# AJH_as3320_21_4hp.net
KiCad netlist of a schematic drawn in EAGLE
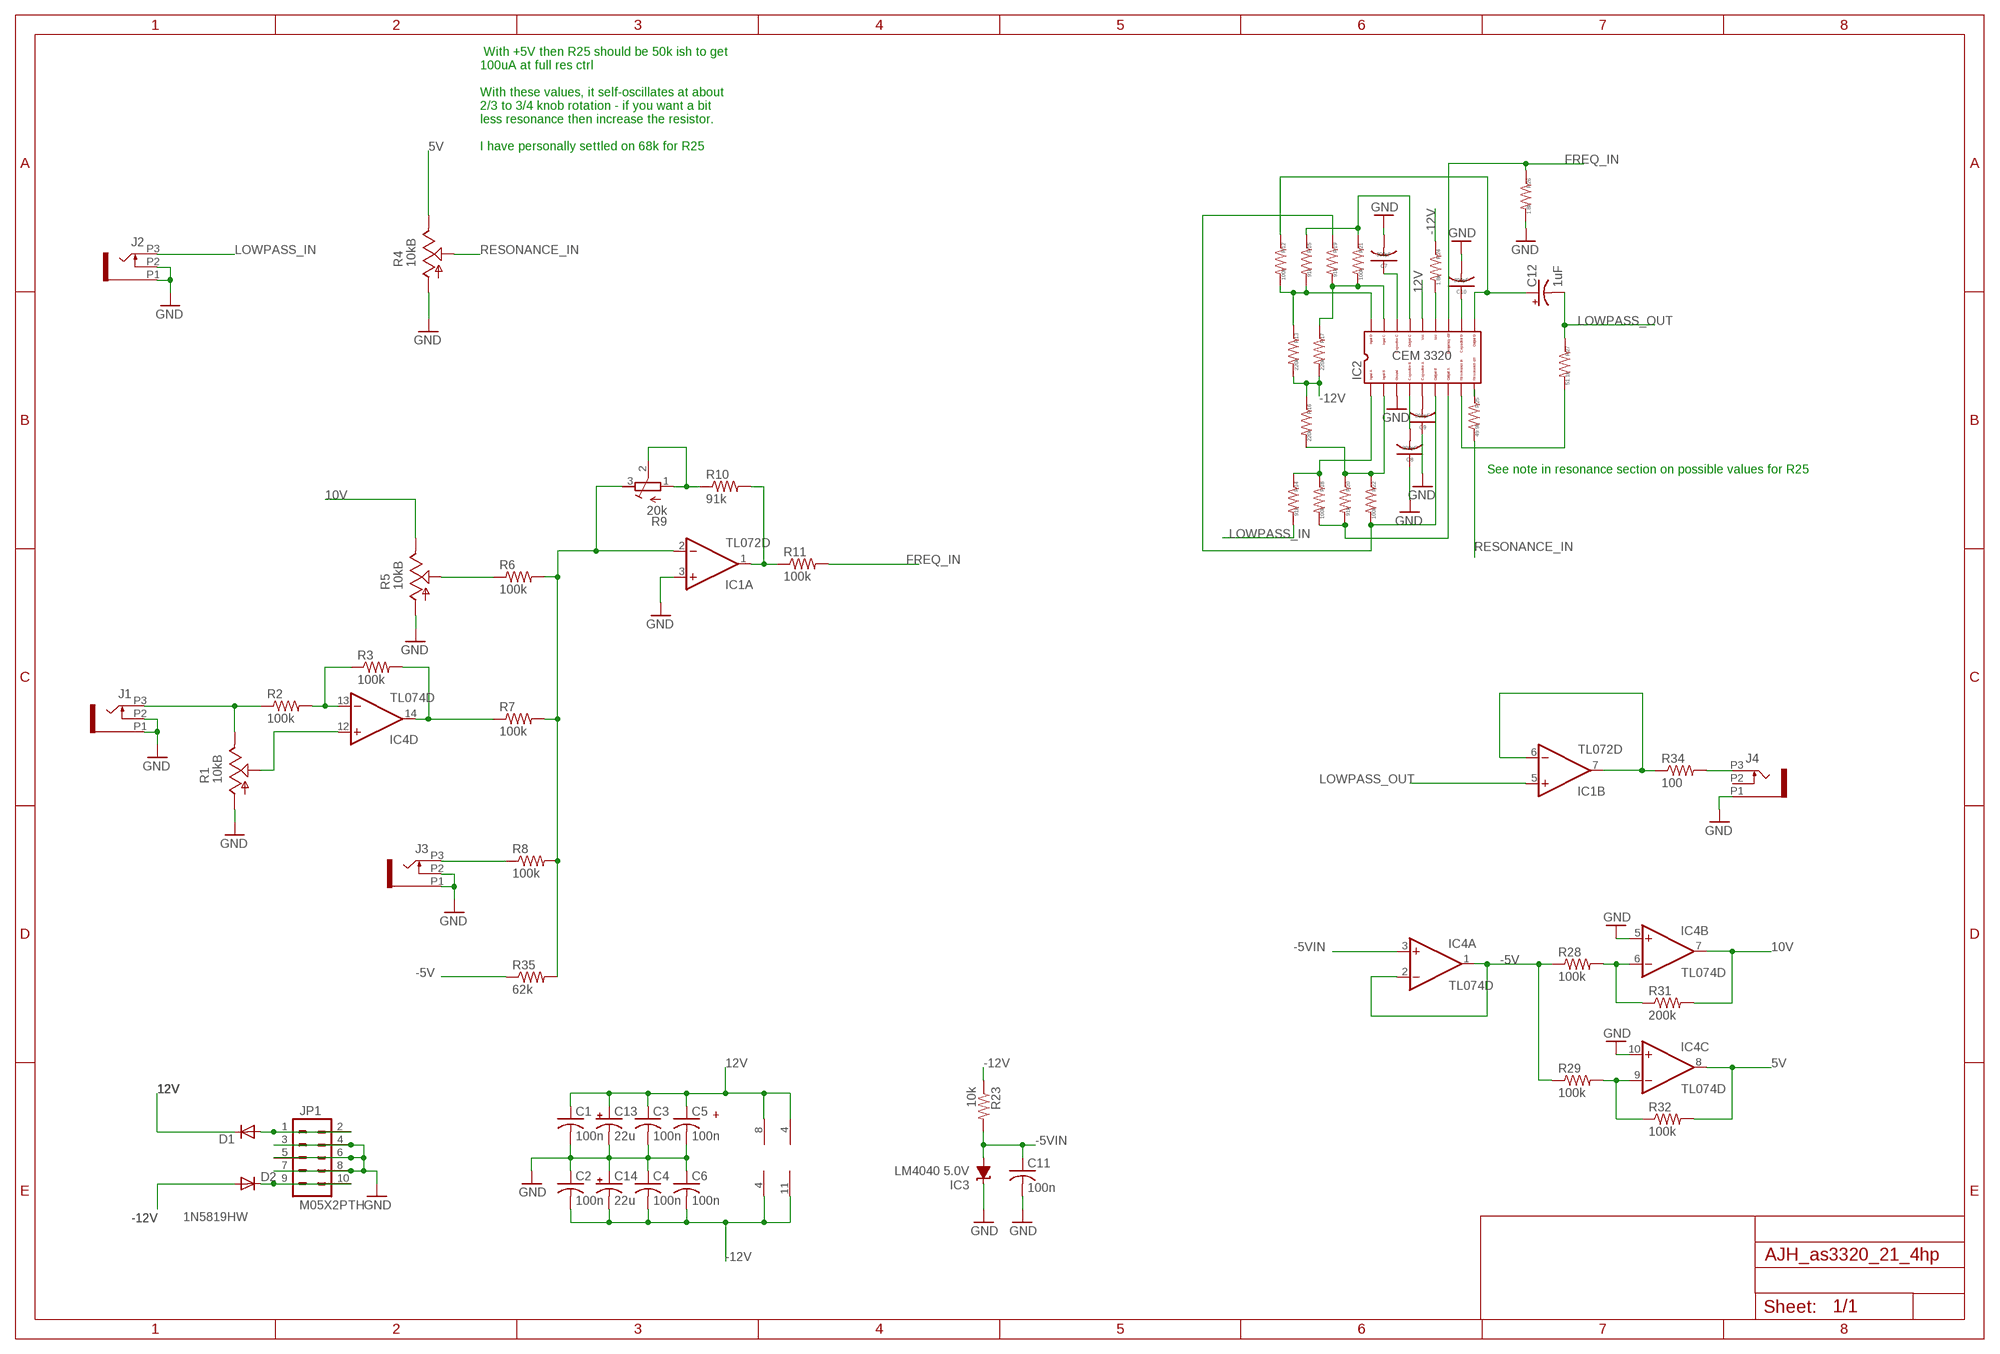
[diagram p0: schematic, sheet 1]

(export (version "E")
  (design (tool "Eeschema 10.0.6"))
  (components
    (comp (ref "C1")
      (value "100n")
      (footprint "eagle-import:C0603")
      (libsource (lib "eagle-import") (part "C-USC0603"))
    )
    (comp (ref "C2")
      (value "100n")
      (footprint "eagle-import:C0603")
      (libsource (lib "eagle-import") (part "C-USC0603"))
    )
    (comp (ref "C3")
      (value "100n")
      (footprint "eagle-import:C0603")
      (libsource (lib "eagle-import") (part "C-USC0603"))
    )
    (comp (ref "C4")
      (value "100n")
      (footprint "eagle-import:C0603")
      (libsource (lib "eagle-import") (part "C-USC0603"))
    )
    (comp (ref "C5")
      (value "100n")
      (footprint "eagle-import:C0603")
      (libsource (lib "eagle-import") (part "C-USC0603"))
    )
    (comp (ref "C6")
      (value "100n")
      (footprint "eagle-import:C0603")
      (libsource (lib "eagle-import") (part "C-USC0603"))
    )
    (comp (ref "C7")
      (value "300pF")
      (footprint "eagle-import:C0603")
      (libsource (lib "eagle-import") (part "rcl_334_C-USC0603"))
    )
    (comp (ref "C8")
      (value "300pF")
      (footprint "eagle-import:C0603")
      (libsource (lib "eagle-import") (part "rcl_334_C-USC0603"))
    )
    (comp (ref "C9")
      (value "300pF")
      (footprint "eagle-import:C0603")
      (libsource (lib "eagle-import") (part "rcl_334_C-USC0603"))
    )
    (comp (ref "C10")
      (value "300pF")
      (footprint "eagle-import:C0603")
      (libsource (lib "eagle-import") (part "rcl_334_C-USC0603"))
    )
    (comp (ref "C11")
      (value "100n")
      (footprint "eagle-import:C0603")
      (libsource (lib "eagle-import") (part "C-USC0603"))
    )
    (comp (ref "C12")
      (value "1uF")
      (footprint "eagle-import:PANASONIC_B")
      (libsource (lib "eagle-import") (part "rcl_334_CPOL-USB"))
    )
    (comp (ref "C13")
      (value "22u")
      (footprint "eagle-import:PANASONIC_B")
      (libsource (lib "eagle-import") (part "CPOL-USB"))
    )
    (comp (ref "C14")
      (value "22u")
      (footprint "eagle-import:PANASONIC_B")
      (libsource (lib "eagle-import") (part "CPOL-USB"))
    )
    (comp (ref "D1")
      (value "1N5819HW")
      (footprint "eagle-import:SOD123")
      (libsource (lib "eagle-import") (part "DIODE-SOD123"))
    )
    (comp (ref "D2")
      (value "1N5819HW")
      (footprint "eagle-import:SOD123")
      (libsource (lib "eagle-import") (part "DIODE-SOD123"))
    )
    (comp (ref "IC1")
      (value "TL072D")
      (footprint "eagle-import:SO08")
      (libsource (lib "eagle-import") (part "TL072D"))
    )
    (comp (ref "IC2")
      (value "CEM3320QFN24")
      (footprint "eagle-import:QFN24")
      (libsource (lib "eagle-import") (part "CEM3320QFN24"))
    )
    (comp (ref "IC3")
      (value "LM4040 5.0V")
      (footprint "eagle-import:DBZ_R-PDSO-G3")
      (libsource (lib "eagle-import") (part "LM4041DBZC12"))
    )
    (comp (ref "IC4")
      (value "TL074D")
      (footprint "eagle-import:SO14")
      (libsource (lib "eagle-import") (part "TL074D"))
    )
    (comp (ref "J1")
      (value "PJ301_THONKICONN6")
      (footprint "eagle-import:WQP_PJ_301M6")
      (libsource (lib "eagle-import") (part "PJ301_THONKICONN6"))
    )
    (comp (ref "J2")
      (value "PJ301_THONKICONN6")
      (footprint "eagle-import:WQP_PJ_301M6")
      (libsource (lib "eagle-import") (part "PJ301_THONKICONN6"))
    )
    (comp (ref "J3")
      (value "PJ301_THONKICONN6")
      (footprint "eagle-import:WQP_PJ_301M6")
      (libsource (lib "eagle-import") (part "PJ301_THONKICONN6"))
    )
    (comp (ref "J4")
      (value "PJ301_THONKICONN6")
      (footprint "eagle-import:WQP_PJ_301M6")
      (libsource (lib "eagle-import") (part "PJ301_THONKICONN6"))
    )
    (comp (ref "JP1")
      (value "M05X2PTH")
      (footprint "eagle-import:AVR_ICSP")
      (libsource (lib "eagle-import") (part "M05X2PTH"))
    )
    (comp (ref "R1")
      (value "10kB")
      (footprint "eagle-import:ALPS_POT_VERTICAL")
      (libsource (lib "eagle-import") (part "POT_USVERTICAL"))
    )
    (comp (ref "R2")
      (value "100k")
      (footprint "eagle-import:R0603")
      (libsource (lib "eagle-import") (part "resistor_R-US_R0603"))
    )
    (comp (ref "R3")
      (value "100k")
      (footprint "eagle-import:R0603")
      (libsource (lib "eagle-import") (part "resistor_R-US_R0603"))
    )
    (comp (ref "R4")
      (value "10kB")
      (footprint "eagle-import:ALPS_POT_VERTICAL")
      (libsource (lib "eagle-import") (part "POT_USVERTICAL"))
    )
    (comp (ref "R5")
      (value "10kB")
      (footprint "eagle-import:ALPS_POT_VERTICAL")
      (libsource (lib "eagle-import") (part "POT_USVERTICAL"))
    )
    (comp (ref "R6")
      (value "100k")
      (footprint "eagle-import:R0603")
      (libsource (lib "eagle-import") (part "resistor_R-US_R0603"))
    )
    (comp (ref "R7")
      (value "100k")
      (footprint "eagle-import:R0603")
      (libsource (lib "eagle-import") (part "resistor_R-US_R0603"))
    )
    (comp (ref "R8")
      (value "100k")
      (footprint "eagle-import:R0603")
      (libsource (lib "eagle-import") (part "resistor_R-US_R0603"))
    )
    (comp (ref "R9")
      (value "20k")
      (footprint "eagle-import:RTRIM3296X")
      (libsource (lib "eagle-import") (part "R-TRIMM3296X"))
    )
    (comp (ref "R10")
      (value "91k")
      (footprint "eagle-import:R0603")
      (libsource (lib "eagle-import") (part "resistor_R-US_R0603"))
    )
    (comp (ref "R11")
      (value "100k")
      (footprint "eagle-import:R0603")
      (libsource (lib "eagle-import") (part "resistor_R-US_R0603"))
    )
    (comp (ref "R12")
      (value "100k")
      (footprint "eagle-import:R0603")
      (libsource (lib "eagle-import") (part "R-US_R0603"))
    )
    (comp (ref "R13")
      (value "220k")
      (footprint "eagle-import:R0603")
      (libsource (lib "eagle-import") (part "R-US_R0603"))
    )
    (comp (ref "R14")
      (value "91k")
      (footprint "eagle-import:R0603")
      (libsource (lib "eagle-import") (part "R-US_R0603"))
    )
    (comp (ref "R15")
      (value "91k")
      (footprint "eagle-import:R0603")
      (libsource (lib "eagle-import") (part "R-US_R0603"))
    )
    (comp (ref "R16")
      (value "220k")
      (footprint "eagle-import:R0603")
      (libsource (lib "eagle-import") (part "R-US_R0603"))
    )
    (comp (ref "R17")
      (value "220k")
      (footprint "eagle-import:R0603")
      (libsource (lib "eagle-import") (part "R-US_R0603"))
    )
    (comp (ref "R18")
      (value "100k")
      (footprint "eagle-import:R0603")
      (libsource (lib "eagle-import") (part "R-US_R0603"))
    )
    (comp (ref "R19")
      (value "91k")
      (footprint "eagle-import:R0603")
      (libsource (lib "eagle-import") (part "R-US_R0603"))
    )
    (comp (ref "R20")
      (value "91k")
      (footprint "eagle-import:R0603")
      (libsource (lib "eagle-import") (part "R-US_R0603"))
    )
    (comp (ref "R21")
      (value "100k")
      (footprint "eagle-import:R0603")
      (libsource (lib "eagle-import") (part "R-US_R0603"))
    )
    (comp (ref "R22")
      (value "100k")
      (footprint "eagle-import:R0603")
      (libsource (lib "eagle-import") (part "R-US_R0603"))
    )
    (comp (ref "R23")
      (value "10k")
      (footprint "eagle-import:R0603")
      (libsource (lib "eagle-import") (part "resistor_R-US_R0603"))
    )
    (comp (ref "R24")
      (value "1.8k")
      (footprint "eagle-import:R0603")
      (libsource (lib "eagle-import") (part "R-US_R0603"))
    )
    (comp (ref "R25")
      (value "49.9k")
      (footprint "eagle-import:R0603")
      (libsource (lib "eagle-import") (part "R-US_R0603"))
    )
    (comp (ref "R26")
      (value "1.8k")
      (footprint "eagle-import:R0603")
      (libsource (lib "eagle-import") (part "R-US_R0603"))
    )
    (comp (ref "R27")
      (value "51.1k")
      (footprint "eagle-import:R0603")
      (libsource (lib "eagle-import") (part "R-US_R0603"))
    )
    (comp (ref "R28")
      (value "100k")
      (footprint "eagle-import:R0603")
      (libsource (lib "eagle-import") (part "resistor_R-US_R0603"))
    )
    (comp (ref "R29")
      (value "100k")
      (footprint "eagle-import:R0603")
      (libsource (lib "eagle-import") (part "resistor_R-US_R0603"))
    )
    (comp (ref "R31")
      (value "200k")
      (footprint "eagle-import:R0603")
      (libsource (lib "eagle-import") (part "resistor_R-US_R0603"))
    )
    (comp (ref "R32")
      (value "100k")
      (footprint "eagle-import:R0603")
      (libsource (lib "eagle-import") (part "resistor_R-US_R0603"))
    )
    (comp (ref "R34")
      (value "100")
      (footprint "eagle-import:R0603")
      (libsource (lib "eagle-import") (part "resistor_R-US_R0603"))
    )
    (comp (ref "R35")
      (value "62k")
      (footprint "eagle-import:R0603")
      (libsource (lib "eagle-import") (part "resistor_R-US_R0603"))
    )
  )
  (nets
    (net (code "1") (name "/-5V") (class "Default")
      (node (ref "IC4") (pin "1") (pinfunction "OUT_1") (pintype "output"))
      (node (ref "IC4") (pin "2") (pinfunction "-IN_2") (pintype "input"))
      (node (ref "R28") (pin "1") (pinfunction "1_1") (pintype "passive"))
      (node (ref "R29") (pin "1") (pinfunction "1_1") (pintype "passive"))
      (node (ref "R35") (pin "1") (pinfunction "1_1") (pintype "passive"))
    )
    (net (code "2") (name "/-5VIN") (class "Default")
      (node (ref "C11") (pin "1") (pinfunction "1_1") (pintype "passive"))
      (node (ref "IC3") (pin "2") (pinfunction "A_2") (pintype "passive"))
      (node (ref "IC4") (pin "3") (pinfunction "+IN_3") (pintype "input"))
      (node (ref "R23") (pin "2") (pinfunction "2_2") (pintype "passive"))
    )
    (net (code "3") (name "/-12V") (class "Default")
      (node (ref "C14") (pin "-") (pinfunction "-_-") (pintype "passive"))
      (node (ref "C2") (pin "2") (pinfunction "2_2") (pintype "passive"))
      (node (ref "C4") (pin "2") (pinfunction "2_2") (pintype "passive"))
      (node (ref "C6") (pin "2") (pinfunction "2_2") (pintype "passive"))
      (node (ref "D2") (pin "A") (pinfunction "A_A") (pintype "passive"))
      (node (ref "IC1") (pin "4") (pinfunction "V-_4") (pintype "power_in"))
      (node (ref "IC4") (pin "11") (pinfunction "V-_11") (pintype "power_in"))
      (node (ref "R13") (pin "2") (pinfunction "2_2") (pintype "passive"))
      (node (ref "R16") (pin "1") (pinfunction "1_1") (pintype "passive"))
      (node (ref "R17") (pin "2") (pinfunction "2_2") (pintype "passive"))
      (node (ref "R23") (pin "1") (pinfunction "1_1") (pintype "passive"))
      (node (ref "R24") (pin "1") (pinfunction "1_1") (pintype "passive"))
    )
    (net (code "4") (name "/5V") (class "Default")
      (node (ref "IC4") (pin "8") (pinfunction "OUT_8") (pintype "output"))
      (node (ref "R32") (pin "2") (pinfunction "2_2") (pintype "passive"))
      (node (ref "R4") (pin "P$1") (pinfunction "E_P$1") (pintype "passive"))
    )
    (net (code "5") (name "/10V") (class "Default")
      (node (ref "IC4") (pin "7") (pinfunction "OUT_7") (pintype "output"))
      (node (ref "R31") (pin "2") (pinfunction "2_2") (pintype "passive"))
      (node (ref "R5") (pin "P$1") (pinfunction "E_P$1") (pintype "passive"))
    )
    (net (code "6") (name "/12V") (class "Default")
      (node (ref "C1") (pin "1") (pinfunction "1_1") (pintype "passive"))
      (node (ref "C13") (pin "+") (pinfunction "+_+") (pintype "passive"))
      (node (ref "C3") (pin "1") (pinfunction "1_1") (pintype "passive"))
      (node (ref "C5") (pin "1") (pinfunction "1_1") (pintype "passive"))
      (node (ref "D1") (pin "C") (pinfunction "C_C") (pintype "passive"))
      (node (ref "IC1") (pin "8") (pinfunction "V+_8") (pintype "power_in"))
      (node (ref "IC2") (pin "P$22") (pinfunction "14_P$22") (pintype "power_in"))
      (node (ref "IC4") (pin "4") (pinfunction "V+_4") (pintype "power_in"))
    )
    (net (code "7") (name "/FREQ_IN") (class "Default")
      (node (ref "IC2") (pin "P$19") (pinfunction "12_P$19") (pintype "bidirectional"))
      (node (ref "R11") (pin "2") (pinfunction "2_2") (pintype "passive"))
      (node (ref "R26") (pin "1") (pinfunction "1_1") (pintype "passive"))
    )
    (net (code "8") (name "/LOWPASS_IN") (class "Default")
      (node (ref "J2") (pin "P3") (pinfunction "3_P3") (pintype "passive"))
      (node (ref "R14") (pin "2") (pinfunction "2_2") (pintype "passive"))
    )
    (net (code "9") (name "/LOWPASS_OUT") (class "Default")
      (node (ref "C12") (pin "-") (pinfunction "-_-") (pintype "passive"))
      (node (ref "IC1") (pin "5") (pinfunction "+IN_5") (pintype "input"))
      (node (ref "R27") (pin "1") (pinfunction "1_1") (pintype "passive"))
    )
    (net (code "10") (name "/RESONANCE_IN") (class "Default")
      (node (ref "R25") (pin "2") (pinfunction "2_2") (pintype "passive"))
      (node (ref "R4") (pin "P$2") (pinfunction "S_P$2") (pintype "passive"))
    )
    (net (code "11") (name "GND") (class "Default")
      (node (ref "C1") (pin "2") (pinfunction "2_2") (pintype "passive"))
      (node (ref "C10") (pin "2") (pinfunction "2_2") (pintype "passive"))
      (node (ref "C11") (pin "2") (pinfunction "2_2") (pintype "passive"))
      (node (ref "C13") (pin "-") (pinfunction "-_-") (pintype "passive"))
      (node (ref "C14") (pin "+") (pinfunction "+_+") (pintype "passive"))
      (node (ref "C2") (pin "1") (pinfunction "1_1") (pintype "passive"))
      (node (ref "C3") (pin "2") (pinfunction "2_2") (pintype "passive"))
      (node (ref "C4") (pin "1") (pinfunction "1_1") (pintype "passive"))
      (node (ref "C5") (pin "2") (pinfunction "2_2") (pintype "passive"))
      (node (ref "C6") (pin "1") (pinfunction "1_1") (pintype "passive"))
      (node (ref "C7") (pin "2") (pinfunction "2_2") (pintype "passive"))
      (node (ref "C8") (pin "1") (pinfunction "1_1") (pintype "passive"))
      (node (ref "C9") (pin "1") (pinfunction "1_1") (pintype "passive"))
      (node (ref "IC1") (pin "3") (pinfunction "+IN_3") (pintype "input"))
      (node (ref "IC2") (pin "P$7") (pinfunction "3_P$7") (pintype "power_in"))
      (node (ref "IC3") (pin "1") (pinfunction "C_1") (pintype "passive"))
      (node (ref "IC4") (pin "10") (pinfunction "+IN_10") (pintype "input"))
      (node (ref "IC4") (pin "5") (pinfunction "+IN_5") (pintype "input"))
      (node (ref "J1") (pin "P1") (pinfunction "1_P1") (pintype "passive"))
      (node (ref "J1") (pin "P2") (pinfunction "2_P2") (pintype "passive"))
      (node (ref "J2") (pin "P1") (pinfunction "1_P1") (pintype "passive"))
      (node (ref "J2") (pin "P2") (pinfunction "2_P2") (pintype "passive"))
      (node (ref "J3") (pin "P1") (pinfunction "1_P1") (pintype "passive"))
      (node (ref "J3") (pin "P2") (pinfunction "2_P2") (pintype "passive"))
      (node (ref "J4") (pin "P1") (pinfunction "1_P1") (pintype "passive"))
      (node (ref "JP1") (pin "3") (pinfunction "3_3") (pintype "passive"))
      (node (ref "JP1") (pin "4") (pinfunction "4_4") (pintype "passive"))
      (node (ref "JP1") (pin "5") (pinfunction "5_5") (pintype "passive"))
      (node (ref "JP1") (pin "6") (pinfunction "6_6") (pintype "passive"))
      (node (ref "JP1") (pin "7") (pinfunction "7_7") (pintype "passive"))
      (node (ref "JP1") (pin "8") (pinfunction "8_8") (pintype "passive"))
      (node (ref "R1") (pin "P$3") (pinfunction "A_P$3") (pintype "passive"))
      (node (ref "R26") (pin "2") (pinfunction "2_2") (pintype "passive"))
      (node (ref "R4") (pin "P$3") (pinfunction "A_P$3") (pintype "passive"))
      (node (ref "R5") (pin "P$3") (pinfunction "A_P$3") (pintype "passive"))
    )
    (net (code "12") (name "Net-(D1-PadA)") (class "Default")
      (node (ref "D1") (pin "A") (pinfunction "A_A") (pintype "passive"))
      (node (ref "JP1") (pin "1") (pinfunction "1_1") (pintype "passive"))
      (node (ref "JP1") (pin "2") (pinfunction "2_2") (pintype "passive"))
    )
    (net (code "13") (name "Net-(D2-PadC)") (class "Default")
      (node (ref "D2") (pin "C") (pinfunction "C_C") (pintype "passive"))
      (node (ref "JP1") (pin "10") (pinfunction "10_10") (pintype "passive"))
      (node (ref "JP1") (pin "9") (pinfunction "9_9") (pintype "passive"))
    )
    (net (code "14") (name "Net-(IC1A--IN)") (class "Default")
      (node (ref "IC1") (pin "2") (pinfunction "-IN_2") (pintype "input"))
      (node (ref "R35") (pin "2") (pinfunction "2_2") (pintype "passive"))
      (node (ref "R6") (pin "2") (pinfunction "2_2") (pintype "passive"))
      (node (ref "R7") (pin "2") (pinfunction "2_2") (pintype "passive"))
      (node (ref "R8") (pin "2") (pinfunction "2_2") (pintype "passive"))
      (node (ref "R9") (pin "3") (pinfunction "A_3") (pintype "passive"))
    )
    (net (code "15") (name "Net-(IC1A-OUT)") (class "Default")
      (node (ref "IC1") (pin "1") (pinfunction "OUT_1") (pintype "output"))
      (node (ref "R10") (pin "2") (pinfunction "2_2") (pintype "passive"))
      (node (ref "R11") (pin "1") (pinfunction "1_1") (pintype "passive"))
    )
    (net (code "16") (name "Net-(IC1B--IN)") (class "Default")
      (node (ref "IC1") (pin "6") (pinfunction "-IN_6") (pintype "input"))
      (node (ref "IC1") (pin "7") (pinfunction "OUT_7") (pintype "output"))
      (node (ref "R34") (pin "1") (pinfunction "1_1") (pintype "passive"))
    )
    (net (code "17") (name "Net-(IC2-1)") (class "Default")
      (node (ref "IC2") (pin "P$4") (pinfunction "1_P$4") (pintype "input"))
      (node (ref "R14") (pin "1") (pinfunction "1_1") (pintype "passive"))
      (node (ref "R18") (pin "1") (pinfunction "1_1") (pintype "passive"))
    )
    (net (code "18") (name "Net-(IC2-2)") (class "Default")
      (node (ref "IC2") (pin "P$5") (pinfunction "2_P$5") (pintype "input"))
      (node (ref "R16") (pin "2") (pinfunction "2_2") (pintype "passive"))
      (node (ref "R20") (pin "1") (pinfunction "1_1") (pintype "passive"))
      (node (ref "R22") (pin "1") (pinfunction "1_1") (pintype "passive"))
    )
    (net (code "19") (name "Net-(IC2-4)") (class "Default")
      (node (ref "C8") (pin "2") (pinfunction "2_2") (pintype "passive"))
      (node (ref "IC2") (pin "P$8") (pinfunction "4_P$8") (pintype "bidirectional"))
    )
    (net (code "20") (name "Net-(IC2-5)") (class "Default")
      (node (ref "C9") (pin "2") (pinfunction "2_2") (pintype "passive"))
      (node (ref "IC2") (pin "P$9") (pinfunction "5_P$9") (pintype "bidirectional"))
    )
    (net (code "21") (name "Net-(IC2-6)") (class "Default")
      (node (ref "IC2") (pin "P$11") (pinfunction "6_P$11") (pintype "output"))
      (node (ref "R19") (pin "1") (pinfunction "1_1") (pintype "passive"))
      (node (ref "R22") (pin "2") (pinfunction "2_2") (pintype "passive"))
    )
    (net (code "22") (name "Net-(IC2-7)") (class "Default")
      (node (ref "IC2") (pin "P$12") (pinfunction "7_P$12") (pintype "output"))
      (node (ref "R18") (pin "2") (pinfunction "2_2") (pintype "passive"))
      (node (ref "R20") (pin "2") (pinfunction "2_2") (pintype "passive"))
    )
    (net (code "23") (name "Net-(IC2-8)") (class "Default")
      (node (ref "IC2") (pin "P$14") (pinfunction "8_P$14") (pintype "input"))
      (node (ref "R27") (pin "2") (pinfunction "2_2") (pintype "passive"))
    )
    (net (code "24") (name "Net-(IC2-9)") (class "Default")
      (node (ref "IC2") (pin "P$15") (pinfunction "9_P$15") (pintype "input"))
      (node (ref "R25") (pin "1") (pinfunction "1_1") (pintype "passive"))
    )
    (net (code "25") (name "Net-(IC2-10)") (class "Default")
      (node (ref "C12") (pin "+") (pinfunction "+_+") (pintype "passive"))
      (node (ref "IC2") (pin "P$16") (pinfunction "10_P$16") (pintype "output"))
      (node (ref "R12") (pin "1") (pinfunction "1_1") (pintype "passive"))
    )
    (net (code "26") (name "Net-(IC2-11)") (class "Default")
      (node (ref "C10") (pin "1") (pinfunction "1_1") (pintype "passive"))
      (node (ref "IC2") (pin "P$17") (pinfunction "11_P$17") (pintype "output"))
    )
    (net (code "27") (name "Net-(IC2-13)") (class "Default")
      (node (ref "IC2") (pin "P$20") (pinfunction "13_P$20") (pintype "power_in"))
      (node (ref "R24") (pin "2") (pinfunction "2_2") (pintype "passive"))
    )
    (net (code "28") (name "Net-(IC2-15)") (class "Default")
      (node (ref "IC2") (pin "P$23") (pinfunction "15_P$23") (pintype "output"))
      (node (ref "R15") (pin "1") (pinfunction "1_1") (pintype "passive"))
      (node (ref "R21") (pin "1") (pinfunction "1_1") (pintype "passive"))
    )
    (net (code "29") (name "Net-(IC2-16)") (class "Default")
      (node (ref "C7") (pin "1") (pinfunction "1_1") (pintype "passive"))
      (node (ref "IC2") (pin "P$24") (pinfunction "16_P$24") (pintype "bidirectional"))
    )
    (net (code "30") (name "Net-(IC2-17)") (class "Default")
      (node (ref "IC2") (pin "P$2") (pinfunction "17_P$2") (pintype "input"))
      (node (ref "R17") (pin "1") (pinfunction "1_1") (pintype "passive"))
      (node (ref "R19") (pin "2") (pinfunction "2_2") (pintype "passive"))
      (node (ref "R21") (pin "2") (pinfunction "2_2") (pintype "passive"))
    )
    (net (code "31") (name "Net-(IC2-18)") (class "Default")
      (node (ref "IC2") (pin "P$3") (pinfunction "18_P$3") (pintype "input"))
      (node (ref "R12") (pin "2") (pinfunction "2_2") (pintype "passive"))
      (node (ref "R13") (pin "1") (pinfunction "1_1") (pintype "passive"))
      (node (ref "R15") (pin "2") (pinfunction "2_2") (pintype "passive"))
    )
    (net (code "32") (name "Net-(IC4B--IN)") (class "Default")
      (node (ref "IC4") (pin "6") (pinfunction "-IN_6") (pintype "input"))
      (node (ref "R28") (pin "2") (pinfunction "2_2") (pintype "passive"))
      (node (ref "R31") (pin "1") (pinfunction "1_1") (pintype "passive"))
    )
    (net (code "33") (name "Net-(IC4C--IN)") (class "Default")
      (node (ref "IC4") (pin "9") (pinfunction "-IN_9") (pintype "input"))
      (node (ref "R29") (pin "2") (pinfunction "2_2") (pintype "passive"))
      (node (ref "R32") (pin "1") (pinfunction "1_1") (pintype "passive"))
    )
    (net (code "34") (name "Net-(IC4D-+IN)") (class "Default")
      (node (ref "IC4") (pin "12") (pinfunction "+IN_12") (pintype "input"))
      (node (ref "R1") (pin "P$2") (pinfunction "S_P$2") (pintype "passive"))
    )
    (net (code "35") (name "Net-(IC4D--IN)") (class "Default")
      (node (ref "IC4") (pin "13") (pinfunction "-IN_13") (pintype "input"))
      (node (ref "R2") (pin "2") (pinfunction "2_2") (pintype "passive"))
      (node (ref "R3") (pin "1") (pinfunction "1_1") (pintype "passive"))
    )
    (net (code "36") (name "Net-(IC4D-OUT)") (class "Default")
      (node (ref "IC4") (pin "14") (pinfunction "OUT_14") (pintype "output"))
      (node (ref "R3") (pin "2") (pinfunction "2_2") (pintype "passive"))
      (node (ref "R7") (pin "1") (pinfunction "1_1") (pintype "passive"))
    )
    (net (code "37") (name "Net-(J1-3)") (class "Default")
      (node (ref "J1") (pin "P3") (pinfunction "3_P3") (pintype "passive"))
      (node (ref "R1") (pin "P$1") (pinfunction "E_P$1") (pintype "passive"))
      (node (ref "R2") (pin "1") (pinfunction "1_1") (pintype "passive"))
    )
    (net (code "38") (name "Net-(J3-3)") (class "Default")
      (node (ref "J3") (pin "P3") (pinfunction "3_P3") (pintype "passive"))
      (node (ref "R8") (pin "1") (pinfunction "1_1") (pintype "passive"))
    )
    (net (code "39") (name "Net-(J4-3)") (class "Default")
      (node (ref "J4") (pin "P3") (pinfunction "3_P3") (pintype "passive"))
      (node (ref "R34") (pin "2") (pinfunction "2_2") (pintype "passive"))
    )
    (net (code "40") (name "Net-(R5-S)") (class "Default")
      (node (ref "R5") (pin "P$2") (pinfunction "S_P$2") (pintype "passive"))
      (node (ref "R6") (pin "1") (pinfunction "1_1") (pintype "passive"))
    )
    (net (code "41") (name "Net-(R9-E)") (class "Default")
      (node (ref "R10") (pin "1") (pinfunction "1_1") (pintype "passive"))
      (node (ref "R9") (pin "1") (pinfunction "E_1") (pintype "passive"))
      (node (ref "R9") (pin "2") (pinfunction "S_2") (pintype "passive"))
    )
    (net (code "42") (name "unconnected-(J4-2-PadP2)") (class "Default")
      (node (ref "J4") (pin "P2") (pinfunction "2_P2") (pintype "passive"))
    )
  )
)
